# Qwiic_IMU_Bonobo.net
KiCad netlist of a schematic drawn in EAGLE
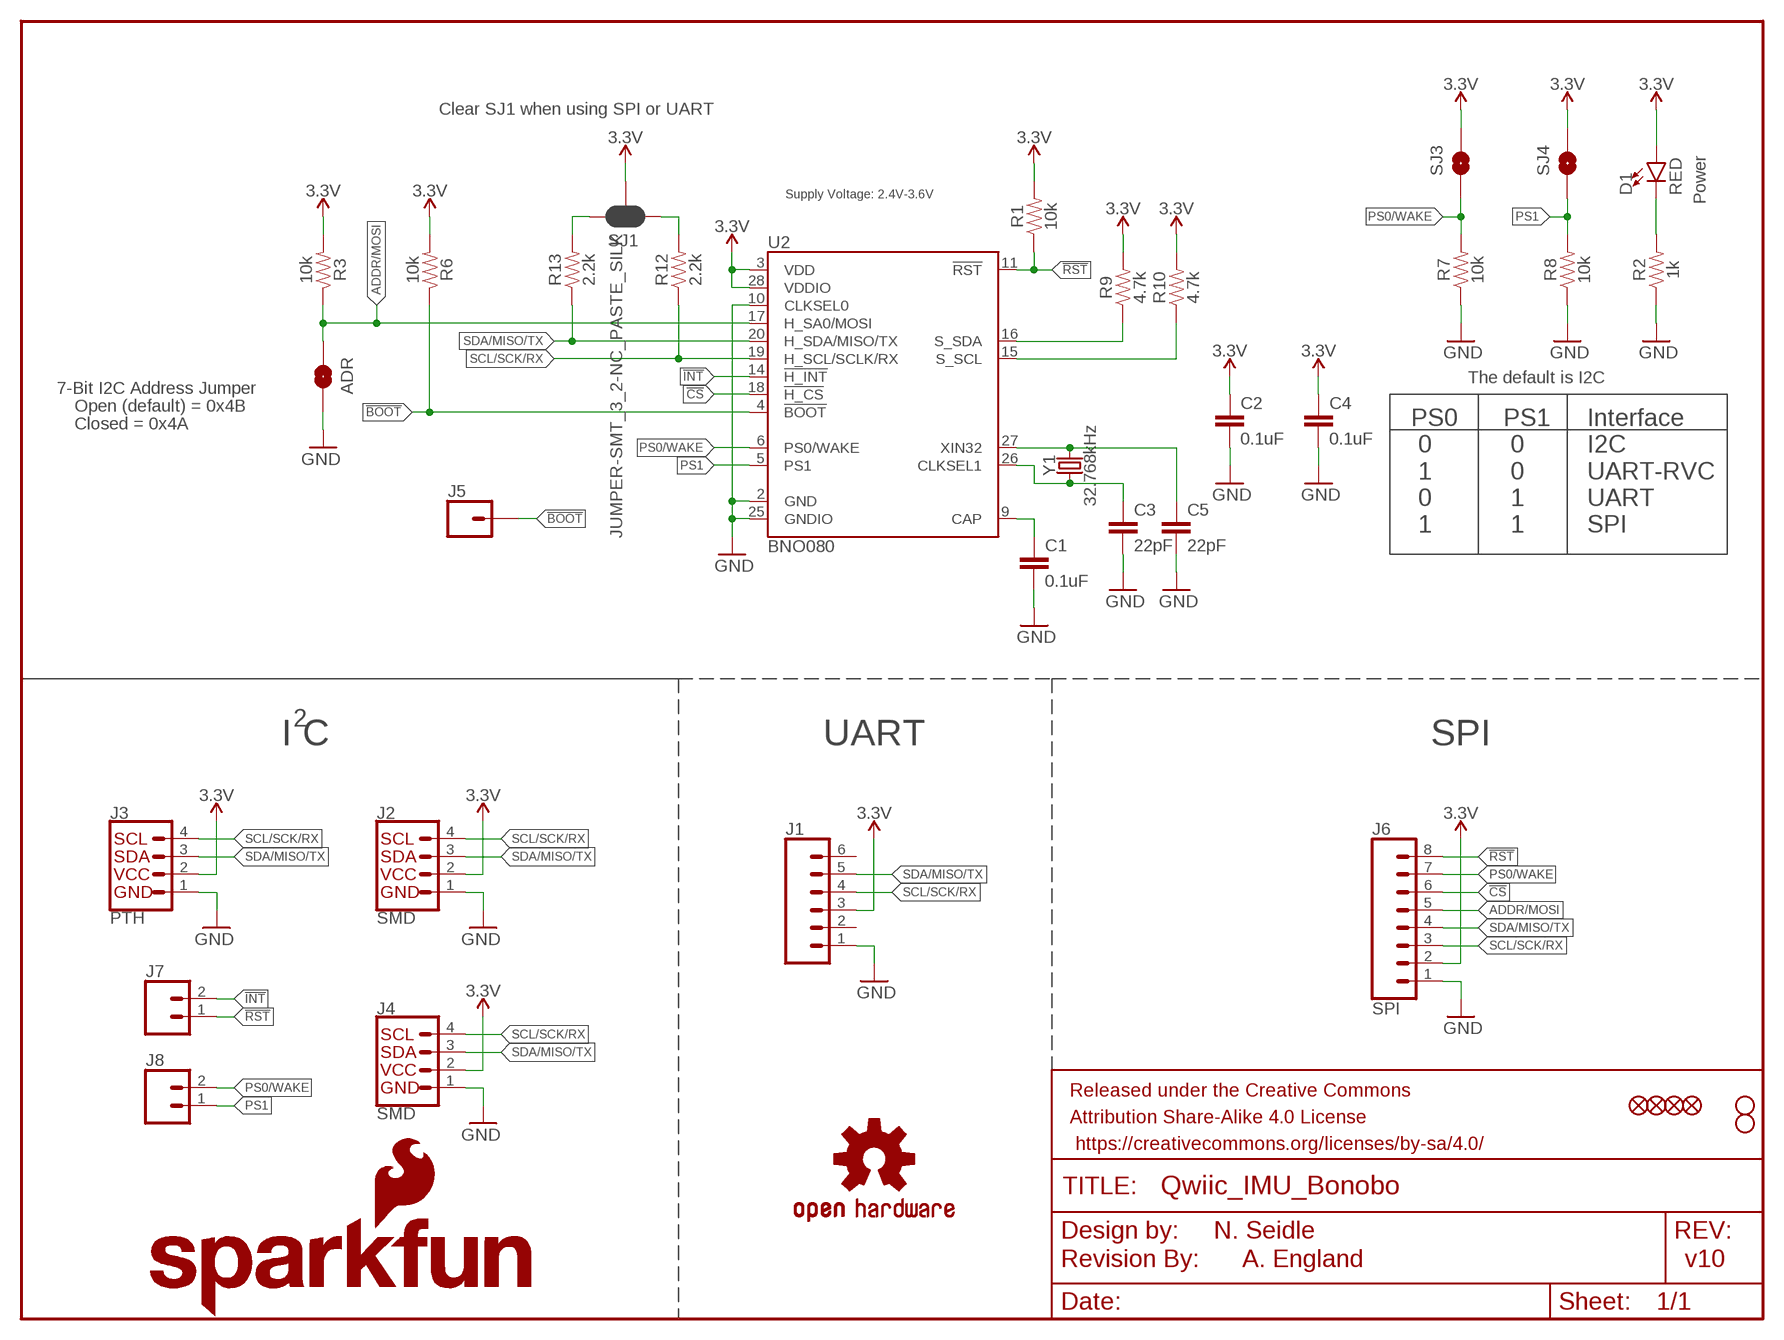
[diagram p0: schematic, sheet 1]

(export (version "E")
  (design (tool "Eeschema 10.0.6"))
  (components
    (comp (ref "ADR")
      (value "JUMPER-SMT_2_NO_SILK")
      (footprint "eagle-import:SMT-JUMPER_2_NO_SILK")
      (libsource (lib "eagle-import") (part "JUMPER-SMT_2_NO_SILK"))
    )
    (comp (ref "C1")
      (value "0.1uF")
      (footprint "eagle-import:0603")
      (libsource (lib "eagle-import") (part "0.1UF-0603-25V-(+80/-20%)"))
    )
    (comp (ref "C2")
      (value "0.1uF")
      (footprint "eagle-import:0603")
      (libsource (lib "eagle-import") (part "0.1UF-0603-25V-(+80/-20%)"))
    )
    (comp (ref "C3")
      (value "22pF")
      (footprint "eagle-import:0603")
      (libsource (lib "eagle-import") (part "22PF-0603-50V-5%"))
    )
    (comp (ref "C4")
      (value "0.1uF")
      (footprint "eagle-import:0603")
      (libsource (lib "eagle-import") (part "0.1UF-0603-25V-(+80/-20%)"))
    )
    (comp (ref "C5")
      (value "22pF")
      (footprint "eagle-import:0603")
      (libsource (lib "eagle-import") (part "22PF-0603-50V-5%"))
    )
    (comp (ref "D1")
      (value "RED")
      (footprint "eagle-import:LED-0603")
      (libsource (lib "eagle-import") (part "LED-RED0603"))
    )
    (comp (ref "FRAME1")
      (value "FRAME-LETTER")
      (footprint "eagle-import:CREATIVE_COMMONS")
      (libsource (lib "eagle-import") (part "FRAME-LETTER"))
    )
    (comp (ref "J1")
      (value "CONN_06NO_SILK_FEMALE_PTH")
      (footprint "eagle-import:1X06_NO_SILK")
      (libsource (lib "eagle-import") (part "CONN_06NO_SILK_FEMALE_PTH"))
    )
    (comp (ref "J2")
      (value "SMD")
      (footprint "eagle-import:1X04_1MM_RA")
      (libsource (lib "eagle-import") (part "I2C_STANDARDJS-1MM"))
    )
    (comp (ref "J3")
      (value "PTH")
      (footprint "eagle-import:1X04_NO_SILK")
      (libsource (lib "eagle-import") (part "I2C_STANDARD_NO_SILK"))
    )
    (comp (ref "J4")
      (value "SMD")
      (footprint "eagle-import:1X04_1MM_RA")
      (libsource (lib "eagle-import") (part "I2C_STANDARDJS-1MM"))
    )
    (comp (ref "J5")
      (value "CONN_01PTH_NO_SILK_YES_STOP")
      (footprint "eagle-import:1X01_NO_SILK")
      (libsource (lib "eagle-import") (part "CONN_01PTH_NO_SILK_YES_STOP"))
    )
    (comp (ref "J6")
      (value "SPI")
      (footprint "eagle-import:1X08_NO_SILK")
      (libsource (lib "eagle-import") (part "CONN_08NO_SILK_FEMALE_PTH"))
    )
    (comp (ref "J7")
      (value "CONN_021X02_NO_SILK")
      (footprint "eagle-import:1X02_NO_SILK")
      (libsource (lib "eagle-import") (part "CONN_021X02_NO_SILK"))
    )
    (comp (ref "J8")
      (value "CONN_021X02_NO_SILK")
      (footprint "eagle-import:1X02_NO_SILK")
      (libsource (lib "eagle-import") (part "CONN_021X02_NO_SILK"))
    )
    (comp (ref "JP1")
      (value "FIDUCIALUFIDUCIAL")
      (footprint "eagle-import:MICRO-FIDUCIAL")
      (libsource (lib "eagle-import") (part "FIDUCIALUFIDUCIAL"))
    )
    (comp (ref "JP2")
      (value "FIDUCIALUFIDUCIAL")
      (footprint "eagle-import:MICRO-FIDUCIAL")
      (libsource (lib "eagle-import") (part "FIDUCIALUFIDUCIAL"))
    )
    (comp (ref "JP3")
      (value "STAND-OFF")
      (footprint "eagle-import:STAND-OFF")
      (libsource (lib "eagle-import") (part "STAND-OFF"))
    )
    (comp (ref "JP4")
      (value "STAND-OFF")
      (footprint "eagle-import:STAND-OFF")
      (libsource (lib "eagle-import") (part "STAND-OFF"))
    )
    (comp (ref "JP5")
      (value "FIDUCIALUFIDUCIAL")
      (footprint "eagle-import:MICRO-FIDUCIAL")
      (libsource (lib "eagle-import") (part "FIDUCIALUFIDUCIAL"))
    )
    (comp (ref "JP6")
      (value "FIDUCIALUFIDUCIAL")
      (footprint "eagle-import:MICRO-FIDUCIAL")
      (libsource (lib "eagle-import") (part "FIDUCIALUFIDUCIAL"))
    )
    (comp (ref "LOGO1")
      (value "OSHW-LOGOMINI")
      (footprint "eagle-import:OSHW-LOGO-MINI")
      (libsource (lib "eagle-import") (part "OSHW-LOGOMINI"))
    )
    (comp (ref "LOGO2")
      (value "REVISION")
      (footprint "eagle-import:REVISION")
      (libsource (lib "eagle-import") (part "REVISION"))
    )
    (comp (ref "LOGO4")
      (value "SFE_LOGO_FLAME.1_INCH")
      (footprint "eagle-import:SFE_LOGO_FLAME_.1")
      (libsource (lib "eagle-import") (part "SFE_LOGO_FLAME.1_INCH"))
    )
    (comp (ref "LOGO5")
      (value "SFE_LOGO_NAME_FLAME.1_INCH")
      (footprint "eagle-import:SFE_LOGO_NAME_FLAME_.1")
      (libsource (lib "eagle-import") (part "SFE_LOGO_NAME_FLAME.1_INCH"))
    )
    (comp (ref "R1")
      (value "10k")
      (footprint "eagle-import:0603")
      (libsource (lib "eagle-import") (part "10KOHM-0603-1/10W-1%"))
    )
    (comp (ref "R2")
      (value "1k")
      (footprint "eagle-import:0603")
      (libsource (lib "eagle-import") (part "1KOHM-0603-1/10W-1%"))
    )
    (comp (ref "R3")
      (value "10k")
      (footprint "eagle-import:0603")
      (libsource (lib "eagle-import") (part "10KOHM-0603-1/10W-1%"))
    )
    (comp (ref "R6")
      (value "10k")
      (footprint "eagle-import:0603")
      (libsource (lib "eagle-import") (part "10KOHM-0603-1/10W-1%"))
    )
    (comp (ref "R7")
      (value "10k")
      (footprint "eagle-import:0603")
      (libsource (lib "eagle-import") (part "10KOHM-0603-1/10W-1%"))
    )
    (comp (ref "R8")
      (value "10k")
      (footprint "eagle-import:0603")
      (libsource (lib "eagle-import") (part "10KOHM-0603-1/10W-1%"))
    )
    (comp (ref "R9")
      (value "4.7k")
      (footprint "eagle-import:0603")
      (libsource (lib "eagle-import") (part "4.7KOHM-0603-1/10W-1%"))
    )
    (comp (ref "R10")
      (value "4.7k")
      (footprint "eagle-import:0603")
      (libsource (lib "eagle-import") (part "4.7KOHM-0603-1/10W-1%"))
    )
    (comp (ref "R12")
      (value "2.2k")
      (footprint "eagle-import:0603")
      (libsource (lib "eagle-import") (part "2.2KOHM-0603-1/10W-1%"))
    )
    (comp (ref "R13")
      (value "2.2k")
      (footprint "eagle-import:0603")
      (libsource (lib "eagle-import") (part "2.2KOHM-0603-1/10W-1%"))
    )
    (comp (ref "SJ1")
      (value "JUMPER-SMT_3_2-NC_PASTE_SILK")
      (footprint "eagle-import:SMT-JUMPER_3_2-NC_PASTE_SILK")
      (libsource (lib "eagle-import") (part "JUMPER-SMT_3_2-NC_PASTE_SILK"))
    )
    (comp (ref "SJ3")
      (value "JUMPER-SMT_2_NO_SILK")
      (footprint "eagle-import:SMT-JUMPER_2_NO_SILK")
      (libsource (lib "eagle-import") (part "JUMPER-SMT_2_NO_SILK"))
    )
    (comp (ref "SJ4")
      (value "JUMPER-SMT_2_NO_SILK")
      (footprint "eagle-import:SMT-JUMPER_2_NO_SILK")
      (libsource (lib "eagle-import") (part "JUMPER-SMT_2_NO_SILK"))
    )
    (comp (ref "U2")
      (value "BNO080")
      (footprint "eagle-import:LGA-28")
      (libsource (lib "eagle-import") (part "BNO080"))
    )
    (comp (ref "Y1")
      (value "32.768kHz")
      (footprint "eagle-import:CRYSTAL-SMD-3.2X1.5MM")
      (libsource (lib "eagle-import") (part "CRYSTAL-32.768KHZSMD-3.2X1.5"))
    )
  )
  (nets
    (net (code "1") (name "/~{BOOT}") (class "Default")
      (node (ref "J5") (pin "1") (pinfunction "1_1") (pintype "passive"))
      (node (ref "R6") (pin "1") (pinfunction "1_1") (pintype "passive"))
      (node (ref "U2") (pin "4") (pinfunction "~{BOOT}_4") (pintype "bidirectional"))
    )
    (net (code "2") (name "/~{CS}") (class "Default")
      (node (ref "J6") (pin "6") (pinfunction "6_6") (pintype "passive"))
      (node (ref "U2") (pin "18") (pinfunction "~{H_CS}_18") (pintype "bidirectional"))
    )
    (net (code "3") (name "/~{INT}") (class "Default")
      (node (ref "J7") (pin "2") (pinfunction "2_2") (pintype "passive"))
      (node (ref "U2") (pin "14") (pinfunction "~{H_INT}_14") (pintype "bidirectional"))
    )
    (net (code "4") (name "/~{RST}") (class "Default")
      (node (ref "J6") (pin "8") (pinfunction "8_8") (pintype "passive"))
      (node (ref "J7") (pin "1") (pinfunction "1_1") (pintype "passive"))
      (node (ref "R1") (pin "1") (pinfunction "1_1") (pintype "passive"))
      (node (ref "U2") (pin "11") (pinfunction "~{RST}_11") (pintype "bidirectional"))
    )
    (net (code "5") (name "3.3V") (class "Default")
      (node (ref "C2") (pin "1") (pinfunction "1_1") (pintype "passive"))
      (node (ref "C4") (pin "1") (pinfunction "1_1") (pintype "passive"))
      (node (ref "D1") (pin "A") (pinfunction "A_A") (pintype "passive"))
      (node (ref "J1") (pin "3") (pinfunction "3_3") (pintype "passive"))
      (node (ref "J2") (pin "2") (pinfunction "VCC_2") (pintype "power_in"))
      (node (ref "J3") (pin "2") (pinfunction "VCC_2") (pintype "power_in"))
      (node (ref "J4") (pin "2") (pinfunction "VCC_2") (pintype "power_in"))
      (node (ref "J6") (pin "2") (pinfunction "2_2") (pintype "passive"))
      (node (ref "R1") (pin "2") (pinfunction "2_2") (pintype "passive"))
      (node (ref "R10") (pin "2") (pinfunction "2_2") (pintype "passive"))
      (node (ref "R3") (pin "2") (pinfunction "2_2") (pintype "passive"))
      (node (ref "R6") (pin "2") (pinfunction "2_2") (pintype "passive"))
      (node (ref "R9") (pin "2") (pinfunction "2_2") (pintype "passive"))
      (node (ref "SJ1") (pin "2") (pinfunction "2_2") (pintype "passive"))
      (node (ref "SJ3") (pin "1") (pinfunction "1_1") (pintype "passive"))
      (node (ref "SJ4") (pin "1") (pinfunction "1_1") (pintype "passive"))
      (node (ref "U2") (pin "28") (pinfunction "VDDIO_28") (pintype "bidirectional"))
      (node (ref "U2") (pin "3") (pinfunction "VDD_3") (pintype "bidirectional"))
    )
    (net (code "6") (name "ADDR{slash}MOSI") (class "Default")
      (node (ref "ADR") (pin "2") (pinfunction "2_2") (pintype "passive"))
      (node (ref "J6") (pin "5") (pinfunction "5_5") (pintype "passive"))
      (node (ref "R3") (pin "1") (pinfunction "1_1") (pintype "passive"))
      (node (ref "U2") (pin "17") (pinfunction "H_SA0/MOSI_17") (pintype "bidirectional"))
    )
    (net (code "7") (name "GND") (class "Default")
      (node (ref "ADR") (pin "1") (pinfunction "1_1") (pintype "passive"))
      (node (ref "C1") (pin "2") (pinfunction "2_2") (pintype "passive"))
      (node (ref "C2") (pin "2") (pinfunction "2_2") (pintype "passive"))
      (node (ref "C3") (pin "2") (pinfunction "2_2") (pintype "passive"))
      (node (ref "C4") (pin "2") (pinfunction "2_2") (pintype "passive"))
      (node (ref "C5") (pin "2") (pinfunction "2_2") (pintype "passive"))
      (node (ref "J1") (pin "1") (pinfunction "1_1") (pintype "passive"))
      (node (ref "J2") (pin "1") (pinfunction "GND_1") (pintype "power_in"))
      (node (ref "J3") (pin "1") (pinfunction "GND_1") (pintype "power_in"))
      (node (ref "J4") (pin "1") (pinfunction "GND_1") (pintype "power_in"))
      (node (ref "J6") (pin "1") (pinfunction "1_1") (pintype "passive"))
      (node (ref "R2") (pin "1") (pinfunction "1_1") (pintype "passive"))
      (node (ref "R7") (pin "1") (pinfunction "1_1") (pintype "passive"))
      (node (ref "R8") (pin "1") (pinfunction "1_1") (pintype "passive"))
      (node (ref "U2") (pin "10") (pinfunction "CLKSEL0_10") (pintype "bidirectional"))
      (node (ref "U2") (pin "2") (pinfunction "GND_2") (pintype "bidirectional"))
      (node (ref "U2") (pin "25") (pinfunction "GNDIO_25") (pintype "bidirectional"))
    )
    (net (code "8") (name "Net-(D1-PadC)") (class "Default")
      (node (ref "D1") (pin "C") (pinfunction "C_C") (pintype "passive"))
      (node (ref "R2") (pin "2") (pinfunction "2_2") (pintype "passive"))
    )
    (net (code "9") (name "Net-(R12-Pad2)") (class "Default")
      (node (ref "R12") (pin "2") (pinfunction "2_2") (pintype "passive"))
      (node (ref "SJ1") (pin "1") (pinfunction "1_1") (pintype "passive"))
    )
    (net (code "10") (name "Net-(R13-Pad2)") (class "Default")
      (node (ref "R13") (pin "2") (pinfunction "2_2") (pintype "passive"))
      (node (ref "SJ1") (pin "3") (pinfunction "3_3") (pintype "passive"))
    )
    (net (code "11") (name "Net-(U2-CAP)") (class "Default")
      (node (ref "C1") (pin "1") (pinfunction "1_1") (pintype "passive"))
      (node (ref "U2") (pin "9") (pinfunction "CAP_9") (pintype "bidirectional"))
    )
    (net (code "12") (name "Net-(U2-CLKSEL1)") (class "Default")
      (node (ref "C3") (pin "1") (pinfunction "1_1") (pintype "passive"))
      (node (ref "U2") (pin "26") (pinfunction "CLKSEL1_26") (pintype "bidirectional"))
      (node (ref "Y1") (pin "P$1") (pinfunction "1_P$1") (pintype "passive"))
    )
    (net (code "13") (name "Net-(U2-S_SCL)") (class "Default")
      (node (ref "R10") (pin "1") (pinfunction "1_1") (pintype "passive"))
      (node (ref "U2") (pin "15") (pinfunction "S_SCL_15") (pintype "bidirectional"))
    )
    (net (code "14") (name "Net-(U2-S_SDA)") (class "Default")
      (node (ref "R9") (pin "1") (pinfunction "1_1") (pintype "passive"))
      (node (ref "U2") (pin "16") (pinfunction "S_SDA_16") (pintype "bidirectional"))
    )
    (net (code "15") (name "Net-(U2-XIN32)") (class "Default")
      (node (ref "C5") (pin "1") (pinfunction "1_1") (pintype "passive"))
      (node (ref "U2") (pin "27") (pinfunction "XIN32_27") (pintype "bidirectional"))
      (node (ref "Y1") (pin "P$2") (pinfunction "2_P$2") (pintype "passive"))
    )
    (net (code "16") (name "PS0{slash}WAKE") (class "Default")
      (node (ref "J6") (pin "7") (pinfunction "7_7") (pintype "passive"))
      (node (ref "J8") (pin "2") (pinfunction "2_2") (pintype "passive"))
      (node (ref "R7") (pin "2") (pinfunction "2_2") (pintype "passive"))
      (node (ref "SJ3") (pin "2") (pinfunction "2_2") (pintype "passive"))
      (node (ref "U2") (pin "6") (pinfunction "PS0/WAKE_6") (pintype "bidirectional"))
    )
    (net (code "17") (name "PS1") (class "Default")
      (node (ref "J8") (pin "1") (pinfunction "1_1") (pintype "passive"))
      (node (ref "R8") (pin "2") (pinfunction "2_2") (pintype "passive"))
      (node (ref "SJ4") (pin "2") (pinfunction "2_2") (pintype "passive"))
      (node (ref "U2") (pin "5") (pinfunction "PS1_5") (pintype "bidirectional"))
    )
    (net (code "18") (name "SCL{slash}SCK{slash}RX") (class "Default")
      (node (ref "J1") (pin "4") (pinfunction "4_4") (pintype "passive"))
      (node (ref "J2") (pin "4") (pinfunction "SCL_4") (pintype "passive"))
      (node (ref "J3") (pin "4") (pinfunction "SCL_4") (pintype "passive"))
      (node (ref "J4") (pin "4") (pinfunction "SCL_4") (pintype "passive"))
      (node (ref "J6") (pin "3") (pinfunction "3_3") (pintype "passive"))
      (node (ref "R12") (pin "1") (pinfunction "1_1") (pintype "passive"))
      (node (ref "U2") (pin "19") (pinfunction "H_SCL/SCLK/RX_19") (pintype "bidirectional"))
    )
    (net (code "19") (name "SDA{slash}MISO{slash}TX") (class "Default")
      (node (ref "J1") (pin "5") (pinfunction "5_5") (pintype "passive"))
      (node (ref "J2") (pin "3") (pinfunction "SDA_3") (pintype "passive"))
      (node (ref "J3") (pin "3") (pinfunction "SDA_3") (pintype "passive"))
      (node (ref "J4") (pin "3") (pinfunction "SDA_3") (pintype "passive"))
      (node (ref "J6") (pin "4") (pinfunction "4_4") (pintype "passive"))
      (node (ref "R13") (pin "1") (pinfunction "1_1") (pintype "passive"))
      (node (ref "U2") (pin "20") (pinfunction "H_SDA/MISO/TX_20") (pintype "bidirectional"))
    )
    (net (code "20") (name "unconnected-(J1-Pad2)") (class "Default")
      (node (ref "J1") (pin "2") (pinfunction "2_2") (pintype "passive"))
    )
    (net (code "21") (name "unconnected-(J1-Pad6)") (class "Default")
      (node (ref "J1") (pin "6") (pinfunction "6_6") (pintype "passive"))
    )
  )
)
